# 40_Pin_BS_FAN_Connector_and_Test_LEDs.net
KiCad netlist of a schematic drawn in Altium Designer
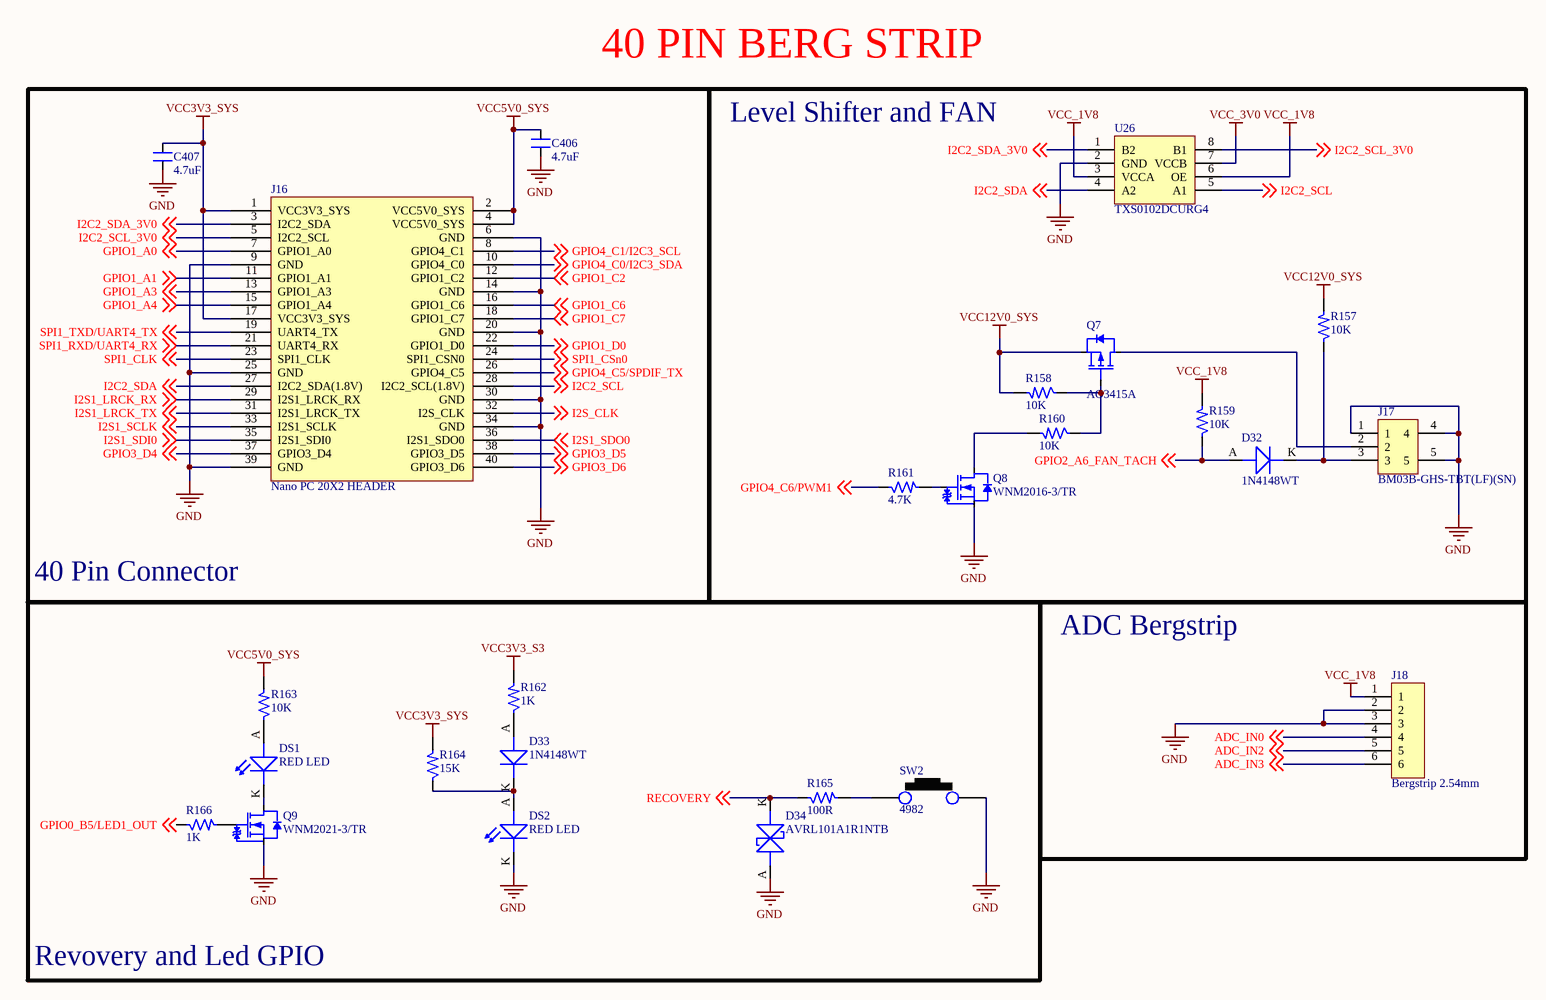
[diagram p0: 40 Pin BS, FAN Connector and Test LEDs.SchDoc]

(export (version "E")
  (design (tool "Eeschema 10.0.6"))
  (components
    (comp (ref "C406")
      (value "4.7uF")
      (footprint "CAP_0603")
      (description "4.7µF ±10% 16V Ceramic Capacitor X5R 0603 (1608 Metric)")
      (fields
        (field (name "MANUFACTURER") "Murata Electronics")
        (field (name "MANUFACTURER PART NUMBER") "GRM188R61C475KAAJD")
      )
      (libsource (lib "RK3399 _Module_Schlib") (part "CAP_4.7uF-16V-10%-0603"))
    )
    (comp (ref "C407")
      (value "4.7uF")
      (footprint "CAP_0603")
      (description "4.7µF ±10% 16V Ceramic Capacitor X5R 0603 (1608 Metric)")
      (fields
        (field (name "MANUFACTURER") "Murata Electronics")
        (field (name "MANUFACTURER PART NUMBER") "GRM188R61C475KAAJD")
      )
      (libsource (lib "RK3399 _Module_Schlib") (part "CAP_4.7uF-16V-10%-0603"))
    )
    (comp (ref "D32")
      (value "1N4148WT")
      (footprint "DIO_SOD523")
      (description "Diode Standard 100V 300mA (DC) Surface Mount SOD-123")
      (fields (field (name "MANUFACTURER") "FAIRCHILD"))
      (libsource (lib "RK3399 _Module_Schlib") (part "DIO_75V-200mA-SOD-523F"))
    )
    (comp (ref "D33")
      (value "1N4148WT")
      (footprint "DIO_SOD523")
      (description "Diode Standard 100V 300mA (DC) Surface Mount SOD-123")
      (fields (field (name "MANUFACTURER") "FAIRCHILD"))
      (libsource (lib "RK3399 _Module_Schlib") (part "DIO_75V-200mA-SOD-523F"))
    )
    (comp (ref "D34")
      (value "AVRL101A1R1NTB")
      (footprint "DIO_0402_SMD")
      (description "39V Varistor 1 Circuit Surface Mount, MLCV 0402 (1005 Metric)")
      (fields (field (name "MANUFACTURER") "TDK Corporation"))
      (libsource (lib "RK3399 _Module_Schlib") (part "DIO-T_10V-39V-0402"))
    )
    (comp (ref "DS1")
      (value "RED LED")
      (footprint "LED_0805")
      (description "Red 631nm LED Indication - Discrete 2V 0805 (2012 Metric)")
      (fields
        (field (name "MANUFACTURER") "Vishay Lite-On")
        (field (name "MANUFACTURER PART NUMBER") "LTST-C171KRKT")
      )
      (libsource (lib "RK3399 _Module_Schlib") (part "LED_RED-2V-20mA-0805"))
    )
    (comp (ref "DS2")
      (value "RED LED")
      (footprint "LED_0805")
      (description "Red 631nm LED Indication - Discrete 2V 0805 (2012 Metric)")
      (fields
        (field (name "MANUFACTURER") "Vishay Lite-On")
        (field (name "MANUFACTURER PART NUMBER") "LTST-C171KRKT")
      )
      (libsource (lib "RK3399 _Module_Schlib") (part "LED_RED-2V-20mA-0805"))
    )
    (comp (ref "J16")
      (value "Nano PC 20X2 HEADER")
      (footprint "CON40_100_ADA2223_ST_TH")
      (description "40 Pins, 2 Row 2.54mm Pitch, Straight bergstrip, Female (Stackup)")
      (fields
        (field (name "MANUFACTURER PART NUMBER") "ADA2223")
        (field (name "MANUFACTURER") "FCI / Amphenol")
      )
      (libsource (lib "RK3399 _Module_Schlib") (part "CON-BS-SKT_20X2-100-ST-TH"))
    )
    (comp (ref "J17")
      (value "BM03B-GHS-TBT(LF)(SN)")
      (footprint "CON3_50_BM03B-GHS-TBT(LF)(SN)_TH_RA")
      (description "Connector Header Surface Mount 3 position 0.049\" (1.25mm)")
      (fields
        (field (name "MANUFACTURER") "JST Sales America Inc.")
        (field (name "NYMBLE PART NUMBER") "1EA-AA-0562")
      )
      (libsource (lib "RK3399 _Module_Schlib") (part "CON-PLG_3X1-50-RA-TH_1"))
    )
    (comp (ref "J18")
      (value "Bergstrip 2.54mm")
      (footprint "CON6_100_59D78_TH_ST")
      (description "6 Pins, 1 Row 2.54mm Pitch, Straight bergstrip, Female")
      (fields (field (name "MANUFACTURER") "Molex") (field (name "MANUFACTURER PART NUMBER") "22-10-2061"))
      (libsource (lib "RK3399 _Module_Schlib") (part "CON-BS-SKT_6X1-100-ST-TH"))
    )
    (comp (ref "Q7")
      (value "AO3415A")
      (footprint "SOT 23-3")
      (description "P-Channel 20V 5A (Ta) 1.5W (Ta) Surface Mount SOT-23-3L")
      (fields (field (name "MANUFACTURER") "Alpha & Omega Semiconductor Inc."))
      (libsource (lib "RK3399 _Module_Schlib") (part "MOSFET-P_20V-5A-SOT23-3"))
    )
    (comp (ref "Q8")
      (value "WNM2016-3/TR")
      (footprint "SOT 23-3")
      (description "N Channel 20V 2.9A 1V @ 250uA 47mΩ @ 3.6A,4.5V 700mW SOT-23(SOT-23-3) MOSFET RoHS")
      (fields (field (name "MANUFACTURER") "WILLSEMI(Will Semicon)"))
      (libsource (lib "EsteemPCB_COB_Course_intlib") (part "MOSFET-N_20V-2.9A-SOT-23"))
    )
    (comp (ref "Q9")
      (value "WNM2021-3/TR")
      (footprint "SOT-323-3")
      (description "N Channel 20V 820mA 850mV @ 250uA 310mΩ @ 550mA,4.5V 310mW SOT-323(SC-70) MOSFET RoHS")
      (fields (field (name "MANUFACTURER") "WILLSEMI(Will Semicon)"))
      (libsource (lib "RK3399 _Module_Schlib") (part "MOSFET-N_20V-820mA-SOT-323"))
    )
    (comp (ref "R157")
      (value "10K")
      (footprint "RES_0603")
      (description "10 kOhms ±1% 0.1W, 1/10W Chip Resistor 0603 (1608 Metric) Thick Film")
      (fields
        (field (name "MANUFACTURER") "Yageo")
        (field (name "MANUFACTURER PART NUMBER") "RC0603FR-0710KL")
      )
      (libsource (lib "RK3399 _Module_Schlib") (part "RES_10K-0.1W-1%-0603"))
    )
    (comp (ref "R158")
      (value "10K")
      (footprint "RES_0603")
      (description "10 kOhms ±1% 0.1W, 1/10W Chip Resistor 0603 (1608 Metric) Thick Film")
      (fields
        (field (name "MANUFACTURER") "Yageo")
        (field (name "MANUFACTURER PART NUMBER") "RC0603FR-0710KL")
      )
      (libsource (lib "RK3399 _Module_Schlib") (part "RES_10K-0.1W-1%-0603"))
    )
    (comp (ref "R159")
      (value "10K")
      (footprint "RES_0603")
      (description "10 kOhms ±1% 0.1W, 1/10W Chip Resistor 0603 (1608 Metric) Thick Film")
      (fields
        (field (name "MANUFACTURER") "Yageo")
        (field (name "MANUFACTURER PART NUMBER") "RC0603FR-0710KL")
      )
      (libsource (lib "RK3399 _Module_Schlib") (part "RES_10K-0.1W-1%-0603"))
    )
    (comp (ref "R160")
      (value "10K")
      (footprint "RES_0603")
      (description "10 kOhms ±1% 0.1W, 1/10W Chip Resistor 0603 (1608 Metric) Thick Film")
      (fields
        (field (name "MANUFACTURER") "Yageo")
        (field (name "MANUFACTURER PART NUMBER") "RC0603FR-0710KL")
      )
      (libsource (lib "RK3399 _Module_Schlib") (part "RES_10K-0.1W-1%-0603"))
    )
    (comp (ref "R161")
      (value "4.7K")
      (footprint "RES_0603")
      (fields
        (field (name "MANUFACTURER") "TE Connectivity Passive Product")
        (field (name "MANUFACTURER PART NUMBER") "CRGCQ0603F4K7")
      )
      (libsource (lib "RK3399 _Module_Schlib") (part "RES_4.7K-0.1W-1%-0603"))
    )
    (comp (ref "R162")
      (value "1K")
      (footprint "RES_0603")
      (description "1 kOhms ±1% 0.1W, 1/10W Chip Resistor 0603 (1608 Metric) Thick Film")
      (fields
        (field (name "MANUFACTURER") "Yageo")
        (field (name "MANUFACTURER PART NUMBER") "RC0603FR-071KL")
      )
      (libsource (lib "RK3399 _Module_Schlib") (part "RES_1K-0.1W-1%-0603"))
    )
    (comp (ref "R163")
      (value "10K")
      (footprint "RES_0603")
      (description "10 kOhms ±1% 0.1W, 1/10W Chip Resistor 0603 (1608 Metric) Thick Film")
      (fields
        (field (name "MANUFACTURER") "Yageo")
        (field (name "MANUFACTURER PART NUMBER") "RC0603FR-0710KL")
      )
      (libsource (lib "RK3399 _Module_Schlib") (part "RES_10K-0.1W-1%-0603"))
    )
    (comp (ref "R164")
      (value "15K")
      (footprint "RES_0603")
      (description "15 kOhms ±1% 0.1W, 1/10W Chip Resistor 0603 (1608 Metric) Thick Film")
      (fields
        (field (name "MANUFACTURER") "Yageo")
        (field (name "MANUFACTURER PART NUMBER") "RC0603FR-0715KL")
      )
      (libsource (lib "RK3399 _Module_Schlib") (part "RES_15K-0.1W-1%-0603"))
    )
    (comp (ref "R165")
      (value "100R")
      (footprint "RES_0603")
      (description "100 Ohms ±1% 0.1W, 1/10W Chip Resistor 0603 (1608 Metric) Thick Film")
      (fields
        (field (name "MANUFACTURER") "Yageo")
        (field (name "MANUFACTURER PART NUMBER") "RC0603FR-07100RL")
      )
      (libsource (lib "RK3399 _Module_Schlib") (part "RES_100R-0.1W-1%-0603"))
    )
    (comp (ref "R166")
      (value "1K")
      (footprint "RES_0603")
      (description "1 kOhms ±1% 0.1W, 1/10W Chip Resistor 0603 (1608 Metric) Thick Film")
      (fields
        (field (name "MANUFACTURER") "Yageo")
        (field (name "MANUFACTURER PART NUMBER") "RC0603FR-071KL")
      )
      (libsource (lib "RK3399 _Module_Schlib") (part "RES_1K-0.1W-1%-0603"))
    )
    (comp (ref "SW2")
      (value "4982")
      (footprint "SW_177_39.3X77.7_SMD")
      (description "Tactile Switch 3x4x2mm SMD 2-Pin")
      (fields (field (name "MANUFACTURER") "NA"))
      (libsource (lib "EsteemPCB_COB_Course_intlib") (part "SW1_4982"))
    )
    (comp (ref "U26")
      (value "TXS0102DCURG4")
      (footprint "VSSOP-8_19.6_157_33X11_SMD")
      (description "Voltage Level Translator Bidirectional 1 Circuit 2 Channel 24Mbps 8-VSSOP")
      (fields (field (name "MANUFACTURER") "Texas Instruments"))
      (libsource (lib "RK3399 _Module_Schlib") (part "IC_TXS0102DCURG4"))
    )
  )
  (nets
    (net (code "1") (name "ADC_IN0") (class "Default")
      (node (ref "J18") (pin "4") (pinfunction "4_4") (pintype "passive"))
    )
    (net (code "2") (name "ADC_IN2") (class "Default")
      (node (ref "J18") (pin "5") (pinfunction "5_5") (pintype "passive"))
    )
    (net (code "3") (name "ADC_IN3") (class "Default")
      (node (ref "J18") (pin "6") (pinfunction "6_6") (pintype "passive"))
    )
    (net (code "4") (name "GND") (class "Default")
      (node (ref "C406") (pin "1") (pinfunction "1_1") (pintype "passive"))
      (node (ref "C407") (pin "1") (pinfunction "1_1") (pintype "passive"))
      (node (ref "D34") (pin "A") (pinfunction "A_A") (pintype "passive"))
      (node (ref "DS2") (pin "K") (pinfunction "CATHODE_K") (pintype "passive"))
      (node (ref "J16") (pin "14") (pinfunction "GND_14") (pintype "passive"))
      (node (ref "J16") (pin "20") (pinfunction "GND_20") (pintype "passive"))
      (node (ref "J16") (pin "25") (pinfunction "GND_25") (pintype "passive"))
      (node (ref "J16") (pin "30") (pinfunction "GND_30") (pintype "passive"))
      (node (ref "J16") (pin "34") (pinfunction "GND_34") (pintype "passive"))
      (node (ref "J16") (pin "39") (pinfunction "GND_39") (pintype "passive"))
      (node (ref "J16") (pin "6") (pinfunction "GND_6") (pintype "passive"))
      (node (ref "J16") (pin "9") (pinfunction "GND_9") (pintype "passive"))
      (node (ref "J17") (pin "1") (pinfunction "1_1") (pintype "passive"))
      (node (ref "J17") (pin "4") (pinfunction "4_4") (pintype "passive"))
      (node (ref "J17") (pin "5") (pinfunction "5_5") (pintype "passive"))
      (node (ref "J18") (pin "2") (pinfunction "2_2") (pintype "passive"))
      (node (ref "J18") (pin "3") (pinfunction "3_3") (pintype "passive"))
      (node (ref "Q8") (pin "2") (pinfunction "S_2") (pintype "passive"))
      (node (ref "Q9") (pin "2") (pinfunction "S_2") (pintype "passive"))
      (node (ref "SW2") (pin "2") (pinfunction "2_2") (pintype "passive"))
      (node (ref "U26") (pin "2") (pinfunction "GND_2") (pintype "passive"))
    )
    (net (code "5") (name "GPIO0_B5{slash}LED1_OUT") (class "Default")
      (node (ref "R166") (pin "1") (pinfunction "1_1") (pintype "passive"))
    )
    (net (code "6") (name "GPIO1_A0") (class "Default")
      (node (ref "J16") (pin "7") (pinfunction "GPIO1_A0_7") (pintype "passive"))
    )
    (net (code "7") (name "GPIO1_A1") (class "Default")
      (node (ref "J16") (pin "11") (pinfunction "GPIO1_A1_11") (pintype "passive"))
    )
    (net (code "8") (name "GPIO1_A3") (class "Default")
      (node (ref "J16") (pin "13") (pinfunction "GPIO1_A3_13") (pintype "passive"))
    )
    (net (code "9") (name "GPIO1_A4") (class "Default")
      (node (ref "J16") (pin "15") (pinfunction "GPIO1_A4_15") (pintype "passive"))
    )
    (net (code "10") (name "GPIO1_C2") (class "Default")
      (node (ref "J16") (pin "12") (pinfunction "GPIO1_C2_12") (pintype "passive"))
    )
    (net (code "11") (name "GPIO1_C6") (class "Default")
      (node (ref "J16") (pin "16") (pinfunction "GPIO1_C6_16") (pintype "passive"))
    )
    (net (code "12") (name "GPIO1_C7") (class "Default")
      (node (ref "J16") (pin "18") (pinfunction "GPIO1_C7_18") (pintype "passive"))
    )
    (net (code "13") (name "GPIO1_D0") (class "Default")
      (node (ref "J16") (pin "22") (pinfunction "GPIO1_D0_22") (pintype "passive"))
    )
    (net (code "14") (name "GPIO2_A6_FAN_TACH") (class "Default")
      (node (ref "D32") (pin "A") (pinfunction "ANODE_A") (pintype "passive"))
      (node (ref "R159") (pin "1") (pinfunction "1_1") (pintype "passive"))
    )
    (net (code "15") (name "GPIO3_D4") (class "Default")
      (node (ref "J16") (pin "37") (pinfunction "GPIO3_D4_37") (pintype "passive"))
    )
    (net (code "16") (name "GPIO3_D5") (class "Default")
      (node (ref "J16") (pin "38") (pinfunction "GPIO3_D5_38") (pintype "passive"))
    )
    (net (code "17") (name "GPIO3_D6") (class "Default")
      (node (ref "J16") (pin "40") (pinfunction "GPIO3_D6_40") (pintype "passive"))
    )
    (net (code "18") (name "GPIO4_C0{slash}I2C3_SDA") (class "Default")
      (node (ref "J16") (pin "10") (pinfunction "GPIO4_C0_10") (pintype "passive"))
    )
    (net (code "19") (name "GPIO4_C1{slash}I2C3_SCL") (class "Default")
      (node (ref "J16") (pin "8") (pinfunction "GPIO4_C1_8") (pintype "passive"))
    )
    (net (code "20") (name "GPIO4_C5{slash}SPDIF_TX") (class "Default")
      (node (ref "J16") (pin "26") (pinfunction "GPIO4_C5_26") (pintype "passive"))
    )
    (net (code "21") (name "GPIO4_C6{slash}PWM1") (class "Default")
      (node (ref "R161") (pin "1") (pinfunction "1_1") (pintype "passive"))
    )
    (net (code "22") (name "I2C2_SCL") (class "Default")
      (node (ref "J16") (pin "28") (pinfunction "I2C2_SCL(1.8V)_28") (pintype "passive"))
      (node (ref "U26") (pin "5") (pinfunction "A1_5") (pintype "passive"))
    )
    (net (code "23") (name "I2C2_SCL_3V0") (class "Default")
      (node (ref "J16") (pin "5") (pinfunction "I2C2_SCL_5") (pintype "passive"))
      (node (ref "U26") (pin "8") (pinfunction "B1_8") (pintype "passive"))
    )
    (net (code "24") (name "I2C2_SDA") (class "Default")
      (node (ref "J16") (pin "27") (pinfunction "I2C2_SDA(1.8V)_27") (pintype "passive"))
      (node (ref "U26") (pin "4") (pinfunction "A2_4") (pintype "passive"))
    )
    (net (code "25") (name "I2C2_SDA_3V0") (class "Default")
      (node (ref "J16") (pin "3") (pinfunction "I2C2_SDA_3") (pintype "passive"))
      (node (ref "U26") (pin "1") (pinfunction "B2_1") (pintype "passive"))
    )
    (net (code "26") (name "I2S1_LRCK_RX") (class "Default")
      (node (ref "J16") (pin "29") (pinfunction "I2S1_LRCK_RX_29") (pintype "passive"))
    )
    (net (code "27") (name "I2S1_LRCK_TX") (class "Default")
      (node (ref "J16") (pin "31") (pinfunction "I2S1_LRCK_TX_31") (pintype "passive"))
    )
    (net (code "28") (name "I2S1_SCLK") (class "Default")
      (node (ref "J16") (pin "33") (pinfunction "I2S1_SCLK_33") (pintype "passive"))
    )
    (net (code "29") (name "I2S1_SDI0") (class "Default")
      (node (ref "J16") (pin "35") (pinfunction "I2S1_SDI0_35") (pintype "passive"))
    )
    (net (code "30") (name "I2S1_SDO0") (class "Default")
      (node (ref "J16") (pin "36") (pinfunction "I2S1_SDO0_36") (pintype "passive"))
    )
    (net (code "31") (name "I2S_CLK") (class "Default")
      (node (ref "J16") (pin "32") (pinfunction "I2S_CLK_32") (pintype "passive"))
    )
    (net (code "32") (name "Net-(D32-CATHODE)") (class "Default")
      (node (ref "D32") (pin "K") (pinfunction "CATHODE_K") (pintype "passive"))
      (node (ref "J17") (pin "3") (pinfunction "3_3") (pintype "passive"))
      (node (ref "R157") (pin "1") (pinfunction "1_1") (pintype "passive"))
    )
    (net (code "33") (name "Net-(D33-ANODE)") (class "Default")
      (node (ref "D33") (pin "A") (pinfunction "ANODE_A") (pintype "passive"))
      (node (ref "R162") (pin "1") (pinfunction "1_1") (pintype "passive"))
    )
    (net (code "34") (name "Net-(D33-CATHODE)") (class "Default")
      (node (ref "D33") (pin "K") (pinfunction "CATHODE_K") (pintype "passive"))
      (node (ref "DS2") (pin "A") (pinfunction "ANODE_A") (pintype "passive"))
      (node (ref "R164") (pin "1") (pinfunction "1_1") (pintype "passive"))
    )
    (net (code "35") (name "Net-(DS1-ANODE)") (class "Default")
      (node (ref "DS1") (pin "A") (pinfunction "ANODE_A") (pintype "passive"))
      (node (ref "R163") (pin "1") (pinfunction "1_1") (pintype "passive"))
    )
    (net (code "36") (name "Net-(DS1-CATHODE)") (class "Default")
      (node (ref "DS1") (pin "K") (pinfunction "CATHODE_K") (pintype "passive"))
      (node (ref "Q9") (pin "3") (pinfunction "D_3") (pintype "passive"))
    )
    (net (code "37") (name "Net-(Q7-D)") (class "Default")
      (node (ref "J17") (pin "2") (pinfunction "2_2") (pintype "passive"))
      (node (ref "Q7") (pin "3") (pinfunction "D_3") (pintype "passive"))
    )
    (net (code "38") (name "Net-(Q7-G)") (class "Default")
      (node (ref "Q7") (pin "1") (pinfunction "G_1") (pintype "passive"))
      (node (ref "R158") (pin "1") (pinfunction "1_1") (pintype "passive"))
      (node (ref "R160") (pin "1") (pinfunction "1_1") (pintype "passive"))
    )
    (net (code "39") (name "Net-(Q8-D)") (class "Default")
      (node (ref "Q8") (pin "3") (pinfunction "D_3") (pintype "passive"))
      (node (ref "R160") (pin "2") (pinfunction "2_2") (pintype "passive"))
    )
    (net (code "40") (name "Net-(Q8-G)") (class "Default")
      (node (ref "Q8") (pin "1") (pinfunction "G_1") (pintype "passive"))
      (node (ref "R161") (pin "2") (pinfunction "2_2") (pintype "passive"))
    )
    (net (code "41") (name "Net-(Q9-G)") (class "Default")
      (node (ref "Q9") (pin "1") (pinfunction "G_1") (pintype "passive"))
      (node (ref "R166") (pin "2") (pinfunction "2_2") (pintype "passive"))
    )
    (net (code "42") (name "Net-(R165-Pad2)") (class "Default")
      (node (ref "R165") (pin "2") (pinfunction "2_2") (pintype "passive"))
      (node (ref "SW2") (pin "1") (pinfunction "1_1") (pintype "passive"))
    )
    (net (code "43") (name "RECOVERY") (class "Default")
      (node (ref "D34") (pin "K") (pinfunction "K_K") (pintype "passive"))
      (node (ref "R165") (pin "1") (pinfunction "1_1") (pintype "passive"))
    )
    (net (code "44") (name "SPI1_CLK") (class "Default")
      (node (ref "J16") (pin "23") (pinfunction "SPI1_CLK_23") (pintype "passive"))
    )
    (net (code "45") (name "SPI1_CSn0") (class "Default")
      (node (ref "J16") (pin "24") (pinfunction "SPI1_CSN0_24") (pintype "passive"))
    )
    (net (code "46") (name "SPI1_RXD{slash}UART4_RX") (class "Default")
      (node (ref "J16") (pin "21") (pinfunction "UART4_RX_21") (pintype "passive"))
    )
    (net (code "47") (name "SPI1_TXD{slash}UART4_TX") (class "Default")
      (node (ref "J16") (pin "19") (pinfunction "UART4_TX_19") (pintype "passive"))
    )
    (net (code "48") (name "VCC3V3_S3") (class "Default")
      (node (ref "R162") (pin "2") (pinfunction "2_2") (pintype "passive"))
    )
    (net (code "49") (name "VCC3V3_SYS") (class "Default")
      (node (ref "C407") (pin "2") (pinfunction "2_2") (pintype "passive"))
      (node (ref "J16") (pin "1") (pinfunction "VCC3V3_SYS_1") (pintype "passive"))
      (node (ref "J16") (pin "17") (pinfunction "VCC3V3_SYS_17") (pintype "passive"))
      (node (ref "R164") (pin "2") (pinfunction "2_2") (pintype "passive"))
    )
    (net (code "50") (name "VCC5V0_SYS") (class "Default")
      (node (ref "C406") (pin "2") (pinfunction "2_2") (pintype "passive"))
      (node (ref "J16") (pin "2") (pinfunction "VCC5V0_SYS_2") (pintype "passive"))
      (node (ref "J16") (pin "4") (pinfunction "VCC5V0_SYS_4") (pintype "passive"))
      (node (ref "R163") (pin "2") (pinfunction "2_2") (pintype "passive"))
    )
    (net (code "51") (name "VCC12V0_SYS") (class "Default")
      (node (ref "Q7") (pin "2") (pinfunction "S_2") (pintype "passive"))
      (node (ref "R157") (pin "2") (pinfunction "2_2") (pintype "passive"))
      (node (ref "R158") (pin "2") (pinfunction "2_2") (pintype "passive"))
    )
    (net (code "52") (name "VCC_1V8") (class "Default")
      (node (ref "J18") (pin "1") (pinfunction "1_1") (pintype "passive"))
      (node (ref "R159") (pin "2") (pinfunction "2_2") (pintype "passive"))
      (node (ref "U26") (pin "3") (pinfunction "VCCA_3") (pintype "passive"))
      (node (ref "U26") (pin "6") (pinfunction "OE_6") (pintype "passive"))
    )
    (net (code "53") (name "VCC_3V0") (class "Default")
      (node (ref "U26") (pin "7") (pinfunction "VCCB_7") (pintype "passive"))
    )
  )
)
